# Powerbox.net
KiCad netlist of a schematic drawn in EAGLE
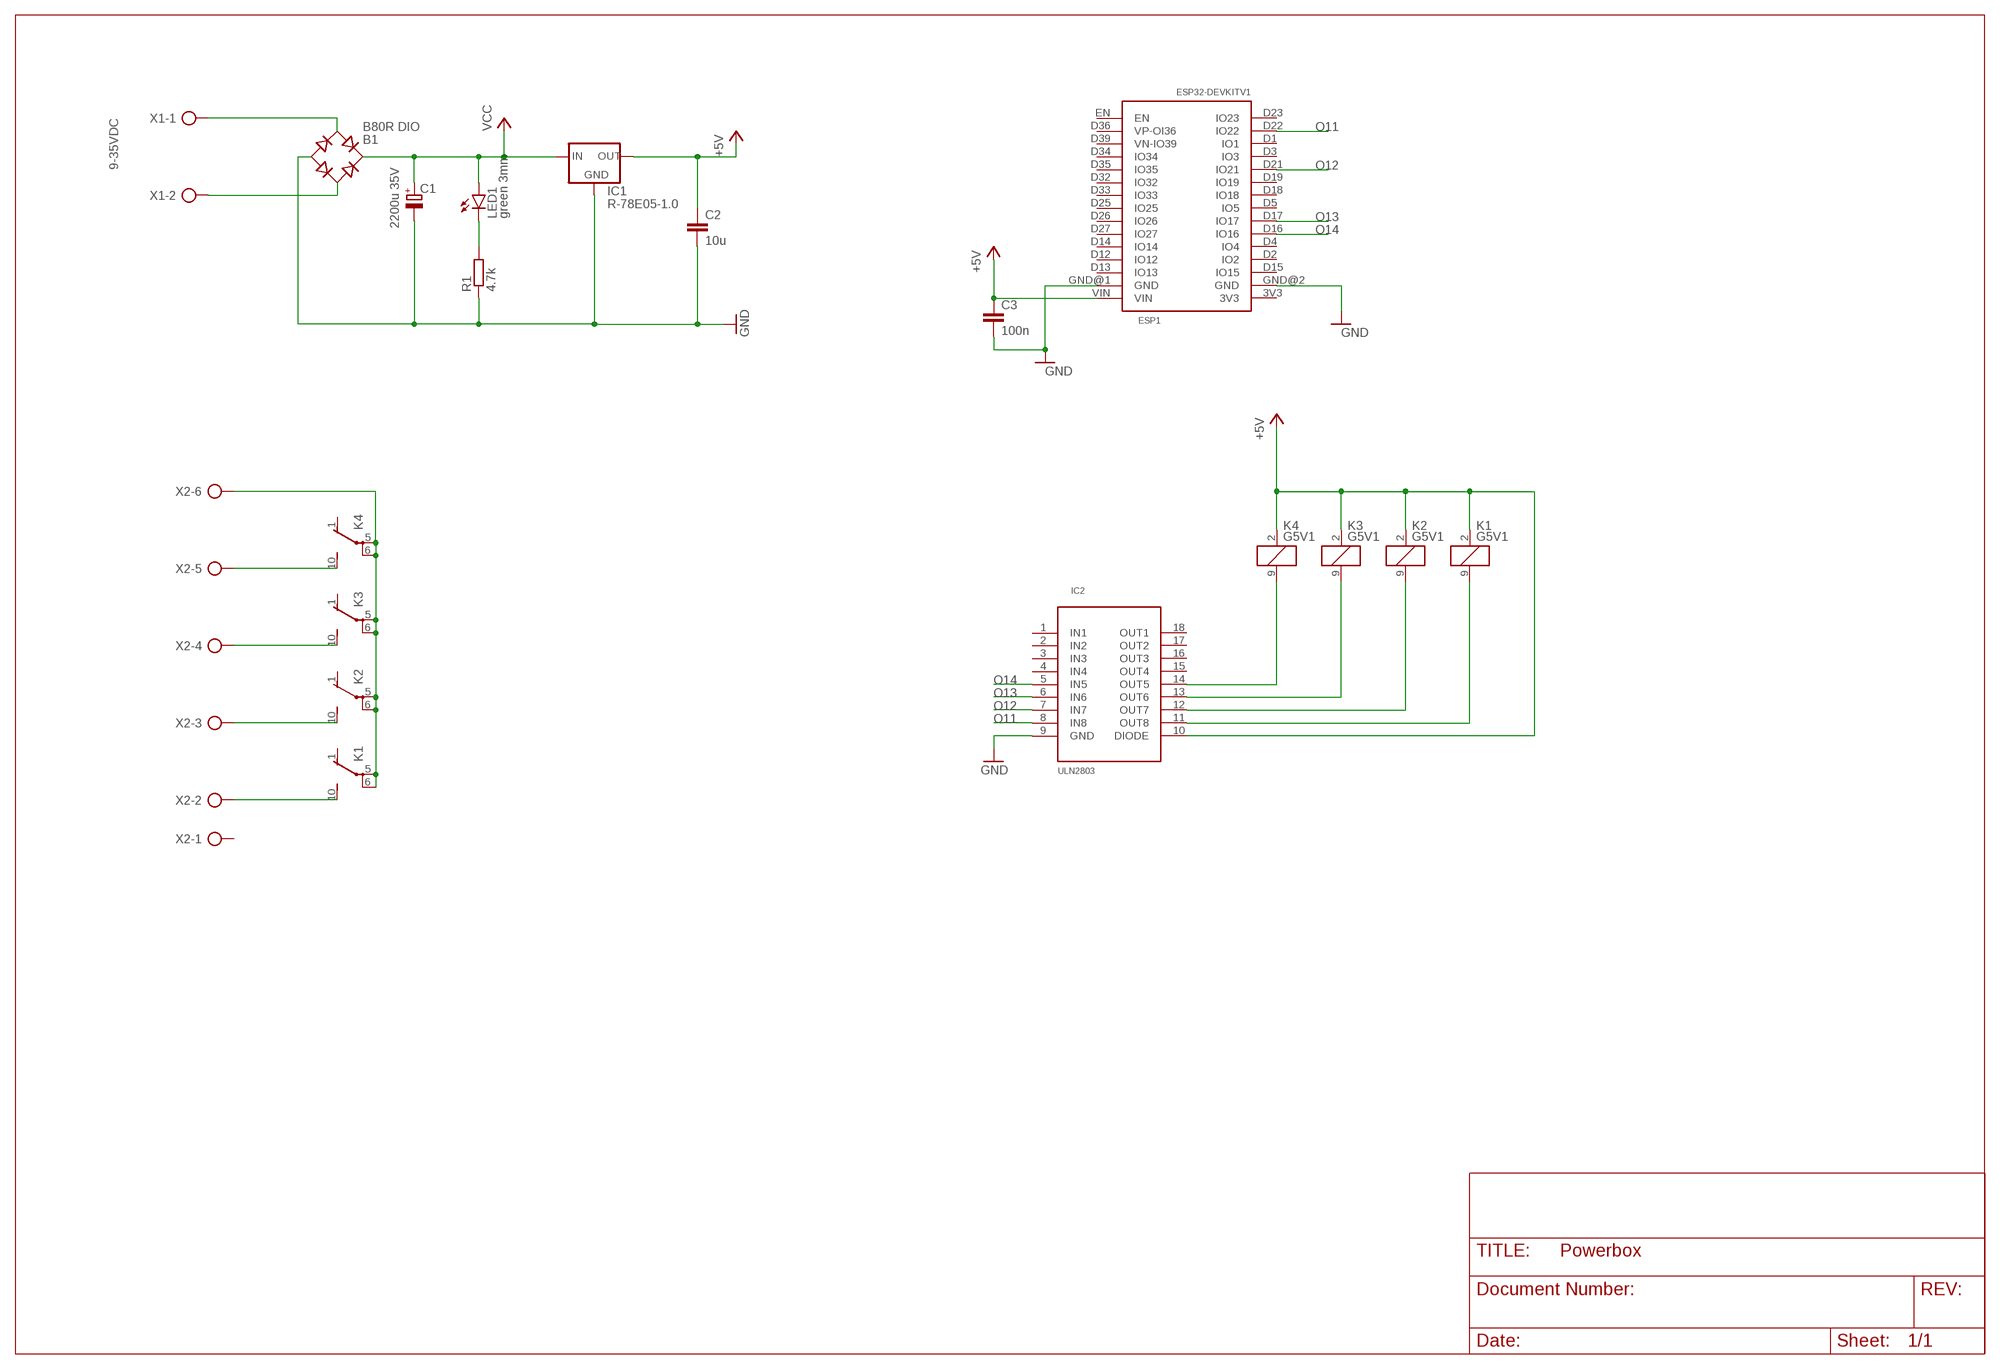
[diagram p0: schematic, sheet 1]

(export (version "E")
  (design (tool "Eeschema 10.0.6"))
  (components
    (comp (ref "B1")
      (value "B80R DIO")
      (footprint "eagle-import:RB1A")
      (libsource (lib "eagle-import") (part "RB1A"))
    )
    (comp (ref "C1")
      (value "2200u 35V")
      (footprint "eagle-import:E5-8,5")
      (libsource (lib "eagle-import") (part "CPOL-EUE5-8.5"))
    )
    (comp (ref "C2")
      (value "10u")
      (footprint "eagle-import:C050-024X044")
      (libsource (lib "eagle-import") (part "C-EU050-024X044"))
    )
    (comp (ref "C3")
      (value "100n")
      (footprint "eagle-import:C050-024X044")
      (libsource (lib "eagle-import") (part "C-EU050-024X044"))
    )
    (comp (ref "ESP1")
      (value "ESP32DEVKITV1")
      (footprint "eagle-import:ESP32-DEVKITV1")
      (libsource (lib "eagle-import") (part "ESP32DEVKITV1"))
    )
    (comp (ref "IC1")
      (value "R-78E05-1.0")
      (footprint "eagle-import:R-78E-XX1.0")
      (libsource (lib "eagle-import") (part "R-78E-XX1.0"))
    )
    (comp (ref "IC2")
      (value "ULN2803")
      (footprint "eagle-import:DIL18")
      (libsource (lib "eagle-import") (part "ULN2803DIL18"))
    )
    (comp (ref "K1")
      (value "G5V1")
      (footprint "eagle-import:G5V1")
      (fields (field (name "MPN") "G5V-1-DC24"))
      (libsource (lib "eagle-import") (part "G5V1"))
    )
    (comp (ref "K2")
      (value "G5V1")
      (footprint "eagle-import:G5V1")
      (fields (field (name "MPN") "G5V-1-DC24"))
      (libsource (lib "eagle-import") (part "G5V1"))
    )
    (comp (ref "K3")
      (value "G5V1")
      (footprint "eagle-import:G5V1")
      (fields (field (name "MPN") "G5V-1-DC24"))
      (libsource (lib "eagle-import") (part "G5V1"))
    )
    (comp (ref "K4")
      (value "G5V1")
      (footprint "eagle-import:G5V1")
      (fields (field (name "MPN") "G5V-1-DC24"))
      (libsource (lib "eagle-import") (part "G5V1"))
    )
    (comp (ref "LED1")
      (value "green 3mm")
      (footprint "eagle-import:LED3MM")
      (fields (field (name "MF") "VISHAY SEMICONDUCTOR"))
      (libsource (lib "eagle-import") (part "TLLG4400"))
    )
    (comp (ref "R1")
      (value "4.7k")
      (footprint "eagle-import:0207_10")
      (libsource (lib "eagle-import") (part "R-EU_0207/10"))
    )
    (comp (ref "X1")
      (value "AK500/2")
      (footprint "eagle-import:AK500_2")
      (libsource (lib "eagle-import") (part "AK500/2"))
    )
    (comp (ref "X2")
      (value "AK500/6")
      (footprint "eagle-import:AK500_6")
      (libsource (lib "eagle-import") (part "AK500/6"))
    )
  )
  (nets
    (net (code "1") (name "+5V") (class "Default")
      (node (ref "C2") (pin "1") (pinfunction "1_1") (pintype "passive"))
      (node (ref "C3") (pin "1") (pinfunction "1_1") (pintype "passive"))
      (node (ref "ESP1") (pin "VIN") (pinfunction "VIN_VIN") (pintype "power_in"))
      (node (ref "IC1") (pin "OUT") (pinfunction "OUT_OUT") (pintype "passive"))
      (node (ref "IC2") (pin "10") (pinfunction "DIODE_10") (pintype "power_in"))
      (node (ref "K1") (pin "2") (pinfunction "1_2") (pintype "passive"))
      (node (ref "K2") (pin "2") (pinfunction "1_2") (pintype "passive"))
      (node (ref "K3") (pin "2") (pinfunction "1_2") (pintype "passive"))
      (node (ref "K4") (pin "2") (pinfunction "1_2") (pintype "passive"))
    )
    (net (code "2") (name "/3V3") (class "Default")
      (node (ref "ESP1") (pin "3V3") (pinfunction "3V3_3V3") (pintype "power_in"))
    )
    (net (code "3") (name "/O11") (class "Default")
      (node (ref "ESP1") (pin "D22") (pinfunction "IO22_D22") (pintype "bidirectional"))
      (node (ref "IC2") (pin "8") (pinfunction "IN8_8") (pintype "input"))
    )
    (net (code "4") (name "/O12") (class "Default")
      (node (ref "ESP1") (pin "D21") (pinfunction "IO21_D21") (pintype "bidirectional"))
      (node (ref "IC2") (pin "7") (pinfunction "IN7_7") (pintype "input"))
    )
    (net (code "5") (name "/O13") (class "Default")
      (node (ref "ESP1") (pin "D17") (pinfunction "IO17_D17") (pintype "bidirectional"))
      (node (ref "IC2") (pin "6") (pinfunction "IN6_6") (pintype "input"))
    )
    (net (code "6") (name "/O14") (class "Default")
      (node (ref "ESP1") (pin "D16") (pinfunction "IO16_D16") (pintype "bidirectional"))
      (node (ref "IC2") (pin "5") (pinfunction "IN5_5") (pintype "input"))
    )
    (net (code "7") (name "GND") (class "Default")
      (node (ref "B1") (pin "-") (pinfunction "-_-") (pintype "passive"))
      (node (ref "C1") (pin "-") (pinfunction "-_-") (pintype "passive"))
      (node (ref "C2") (pin "2") (pinfunction "2_2") (pintype "passive"))
      (node (ref "C3") (pin "2") (pinfunction "2_2") (pintype "passive"))
      (node (ref "ESP1") (pin "GND@1") (pinfunction "GND_GND@1") (pintype "power_in"))
      (node (ref "ESP1") (pin "GND@2") (pinfunction "GND_GND@2") (pintype "power_in"))
      (node (ref "IC1") (pin "GND") (pinfunction "GND_GND") (pintype "input"))
      (node (ref "IC2") (pin "9") (pinfunction "GND_9") (pintype "power_in"))
      (node (ref "R1") (pin "1") (pinfunction "1_1") (pintype "passive"))
    )
    (net (code "8") (name "Net-(IC2-OUT5)") (class "Default")
      (node (ref "IC2") (pin "14") (pinfunction "OUT5_14") (pintype "open_collector"))
      (node (ref "K4") (pin "9") (pinfunction "2_9") (pintype "passive"))
    )
    (net (code "9") (name "Net-(IC2-OUT6)") (class "Default")
      (node (ref "IC2") (pin "13") (pinfunction "OUT6_13") (pintype "open_collector"))
      (node (ref "K3") (pin "9") (pinfunction "2_9") (pintype "passive"))
    )
    (net (code "10") (name "Net-(IC2-OUT7)") (class "Default")
      (node (ref "IC2") (pin "12") (pinfunction "OUT7_12") (pintype "open_collector"))
      (node (ref "K2") (pin "9") (pinfunction "2_9") (pintype "passive"))
    )
    (net (code "11") (name "Net-(IC2-OUT8)") (class "Default")
      (node (ref "IC2") (pin "11") (pinfunction "OUT8_11") (pintype "open_collector"))
      (node (ref "K1") (pin "9") (pinfunction "2_9") (pintype "passive"))
    )
    (net (code "12") (name "Net-(K1B-S)") (class "Default")
      (node (ref "K1") (pin "10") (pinfunction "S_10") (pintype "passive"))
      (node (ref "X2") (pin "2") (pinfunction "KL_2") (pintype "passive"))
    )
    (net (code "13") (name "Net-(K2B-S)") (class "Default")
      (node (ref "K2") (pin "10") (pinfunction "S_10") (pintype "passive"))
      (node (ref "X2") (pin "3") (pinfunction "KL_3") (pintype "passive"))
    )
    (net (code "14") (name "Net-(K3B-S)") (class "Default")
      (node (ref "K3") (pin "10") (pinfunction "S_10") (pintype "passive"))
      (node (ref "X2") (pin "4") (pinfunction "KL_4") (pintype "passive"))
    )
    (net (code "15") (name "Net-(K4B-S)") (class "Default")
      (node (ref "K4") (pin "10") (pinfunction "S_10") (pintype "passive"))
      (node (ref "X2") (pin "5") (pinfunction "KL_5") (pintype "passive"))
    )
    (net (code "16") (name "Net-(LED1-C)") (class "Default")
      (node (ref "LED1") (pin "K") (pinfunction "C_K") (pintype "passive"))
      (node (ref "R1") (pin "2") (pinfunction "2_2") (pintype "passive"))
    )
    (net (code "17") (name "Net-(X1A-KL)") (class "Default")
      (node (ref "B1") (pin "AC1") (pinfunction "AC1_AC1") (pintype "passive"))
      (node (ref "X1") (pin "1") (pinfunction "KL_1") (pintype "passive"))
    )
    (net (code "18") (name "Net-(X1B-KL)") (class "Default")
      (node (ref "B1") (pin "AC2") (pinfunction "AC2_AC2") (pintype "passive"))
      (node (ref "X1") (pin "2") (pinfunction "KL_2") (pintype "passive"))
    )
    (net (code "19") (name "Net-(X2F-KL)") (class "Default")
      (node (ref "K1") (pin "5") (pinfunction "P_5") (pintype "passive"))
      (node (ref "K1") (pin "6") (pinfunction "P_6") (pintype "passive"))
      (node (ref "K2") (pin "5") (pinfunction "P_5") (pintype "passive"))
      (node (ref "K2") (pin "6") (pinfunction "P_6") (pintype "passive"))
      (node (ref "K3") (pin "5") (pinfunction "P_5") (pintype "passive"))
      (node (ref "K3") (pin "6") (pinfunction "P_6") (pintype "passive"))
      (node (ref "K4") (pin "5") (pinfunction "P_5") (pintype "passive"))
      (node (ref "K4") (pin "6") (pinfunction "P_6") (pintype "passive"))
      (node (ref "X2") (pin "6") (pinfunction "KL_6") (pintype "passive"))
    )
    (net (code "20") (name "VCC") (class "Default")
      (node (ref "B1") (pin "+") (pinfunction "+_+") (pintype "passive"))
      (node (ref "C1") (pin "+") (pinfunction "+_+") (pintype "passive"))
      (node (ref "IC1") (pin "IN") (pinfunction "IN_IN") (pintype "input"))
      (node (ref "LED1") (pin "A") (pinfunction "A_A") (pintype "passive"))
    )
    (net (code "21") (name "unconnected-(ESP1-IO1-PadD1)") (class "Default")
      (node (ref "ESP1") (pin "D1") (pinfunction "IO1_D1") (pintype "bidirectional"))
    )
    (net (code "22") (name "unconnected-(ESP1-IO2-PadD2)") (class "Default")
      (node (ref "ESP1") (pin "D2") (pinfunction "IO2_D2") (pintype "bidirectional"))
    )
    (net (code "23") (name "unconnected-(ESP1-IO3-PadD3)") (class "Default")
      (node (ref "ESP1") (pin "D3") (pinfunction "IO3_D3") (pintype "bidirectional"))
    )
    (net (code "24") (name "unconnected-(ESP1-IO4-PadD4)") (class "Default")
      (node (ref "ESP1") (pin "D4") (pinfunction "IO4_D4") (pintype "bidirectional"))
    )
    (net (code "25") (name "unconnected-(ESP1-IO5-PadD5)") (class "Default")
      (node (ref "ESP1") (pin "D5") (pinfunction "IO5_D5") (pintype "bidirectional"))
    )
    (net (code "26") (name "unconnected-(ESP1-IO12-PadD12)") (class "Default")
      (node (ref "ESP1") (pin "D12") (pinfunction "IO12_D12") (pintype "bidirectional"))
    )
    (net (code "27") (name "unconnected-(ESP1-IO13-PadD13)") (class "Default")
      (node (ref "ESP1") (pin "D13") (pinfunction "IO13_D13") (pintype "bidirectional"))
    )
    (net (code "28") (name "unconnected-(ESP1-IO14-PadD14)") (class "Default")
      (node (ref "ESP1") (pin "D14") (pinfunction "IO14_D14") (pintype "bidirectional"))
    )
    (net (code "29") (name "unconnected-(ESP1-IO15-PadD15)") (class "Default")
      (node (ref "ESP1") (pin "D15") (pinfunction "IO15_D15") (pintype "bidirectional"))
    )
    (net (code "30") (name "unconnected-(ESP1-IO18-PadD18)") (class "Default")
      (node (ref "ESP1") (pin "D18") (pinfunction "IO18_D18") (pintype "bidirectional"))
    )
    (net (code "31") (name "unconnected-(ESP1-IO19-PadD19)") (class "Default")
      (node (ref "ESP1") (pin "D19") (pinfunction "IO19_D19") (pintype "bidirectional"))
    )
    (net (code "32") (name "unconnected-(ESP1-IO23-PadD23)") (class "Default")
      (node (ref "ESP1") (pin "D23") (pinfunction "IO23_D23") (pintype "bidirectional"))
    )
    (net (code "33") (name "unconnected-(ESP1-IO25-PadD25)") (class "Default")
      (node (ref "ESP1") (pin "D25") (pinfunction "IO25_D25") (pintype "bidirectional"))
    )
    (net (code "34") (name "unconnected-(ESP1-IO26-PadD26)") (class "Default")
      (node (ref "ESP1") (pin "D26") (pinfunction "IO26_D26") (pintype "bidirectional"))
    )
    (net (code "35") (name "unconnected-(ESP1-IO27-PadD27)") (class "Default")
      (node (ref "ESP1") (pin "D27") (pinfunction "IO27_D27") (pintype "bidirectional"))
    )
    (net (code "36") (name "unconnected-(ESP1-IO32-PadD32)") (class "Default")
      (node (ref "ESP1") (pin "D32") (pinfunction "IO32_D32") (pintype "bidirectional"))
    )
    (net (code "37") (name "unconnected-(ESP1-IO33-PadD33)") (class "Default")
      (node (ref "ESP1") (pin "D33") (pinfunction "IO33_D33") (pintype "bidirectional"))
    )
    (net (code "38") (name "unconnected-(ESP1-IO34-PadD34)") (class "Default")
      (node (ref "ESP1") (pin "D34") (pinfunction "IO34_D34") (pintype "bidirectional"))
    )
    (net (code "39") (name "unconnected-(ESP1-IO35-PadD35)") (class "Default")
      (node (ref "ESP1") (pin "D35") (pinfunction "IO35_D35") (pintype "bidirectional"))
    )
    (net (code "40") (name "unconnected-(ESP1-PadEN)") (class "Default")
      (node (ref "ESP1") (pin "EN") (pinfunction "EN_EN") (pintype "bidirectional"))
    )
    (net (code "41") (name "unconnected-(ESP1-VN-IO39-PadD39)") (class "Default")
      (node (ref "ESP1") (pin "D39") (pinfunction "VN-IO39_D39") (pintype "bidirectional"))
    )
    (net (code "42") (name "unconnected-(ESP1-VP-OI36-PadD36)") (class "Default")
      (node (ref "ESP1") (pin "D36") (pinfunction "VP-OI36_D36") (pintype "bidirectional"))
    )
    (net (code "43") (name "unconnected-(IC2-IN1-Pad1)") (class "Default")
      (node (ref "IC2") (pin "1") (pinfunction "IN1_1") (pintype "input"))
    )
    (net (code "44") (name "unconnected-(IC2-IN2-Pad2)") (class "Default")
      (node (ref "IC2") (pin "2") (pinfunction "IN2_2") (pintype "input"))
    )
    (net (code "45") (name "unconnected-(IC2-IN3-Pad3)") (class "Default")
      (node (ref "IC2") (pin "3") (pinfunction "IN3_3") (pintype "input"))
    )
    (net (code "46") (name "unconnected-(IC2-IN4-Pad4)") (class "Default")
      (node (ref "IC2") (pin "4") (pinfunction "IN4_4") (pintype "input"))
    )
    (net (code "47") (name "unconnected-(IC2-OUT1-Pad18)") (class "Default")
      (node (ref "IC2") (pin "18") (pinfunction "OUT1_18") (pintype "open_collector"))
    )
    (net (code "48") (name "unconnected-(IC2-OUT2-Pad17)") (class "Default")
      (node (ref "IC2") (pin "17") (pinfunction "OUT2_17") (pintype "open_collector"))
    )
    (net (code "49") (name "unconnected-(IC2-OUT3-Pad16)") (class "Default")
      (node (ref "IC2") (pin "16") (pinfunction "OUT3_16") (pintype "open_collector"))
    )
    (net (code "50") (name "unconnected-(IC2-OUT4-Pad15)") (class "Default")
      (node (ref "IC2") (pin "15") (pinfunction "OUT4_15") (pintype "open_collector"))
    )
    (net (code "51") (name "unconnected-(K1B-O-Pad1)") (class "Default")
      (node (ref "K1") (pin "1") (pinfunction "O_1") (pintype "passive"))
    )
    (net (code "52") (name "unconnected-(K2B-O-Pad1)") (class "Default")
      (node (ref "K2") (pin "1") (pinfunction "O_1") (pintype "passive"))
    )
    (net (code "53") (name "unconnected-(K3B-O-Pad1)") (class "Default")
      (node (ref "K3") (pin "1") (pinfunction "O_1") (pintype "passive"))
    )
    (net (code "54") (name "unconnected-(K4B-O-Pad1)") (class "Default")
      (node (ref "K4") (pin "1") (pinfunction "O_1") (pintype "passive"))
    )
    (net (code "55") (name "unconnected-(X2A-KL-Pad1)") (class "Default")
      (node (ref "X2") (pin "1") (pinfunction "KL_1") (pintype "passive"))
    )
  )
)
